# CH32V307_V1_0_0.net
KiCad netlist of a schematic drawn in EasyEDA Pro
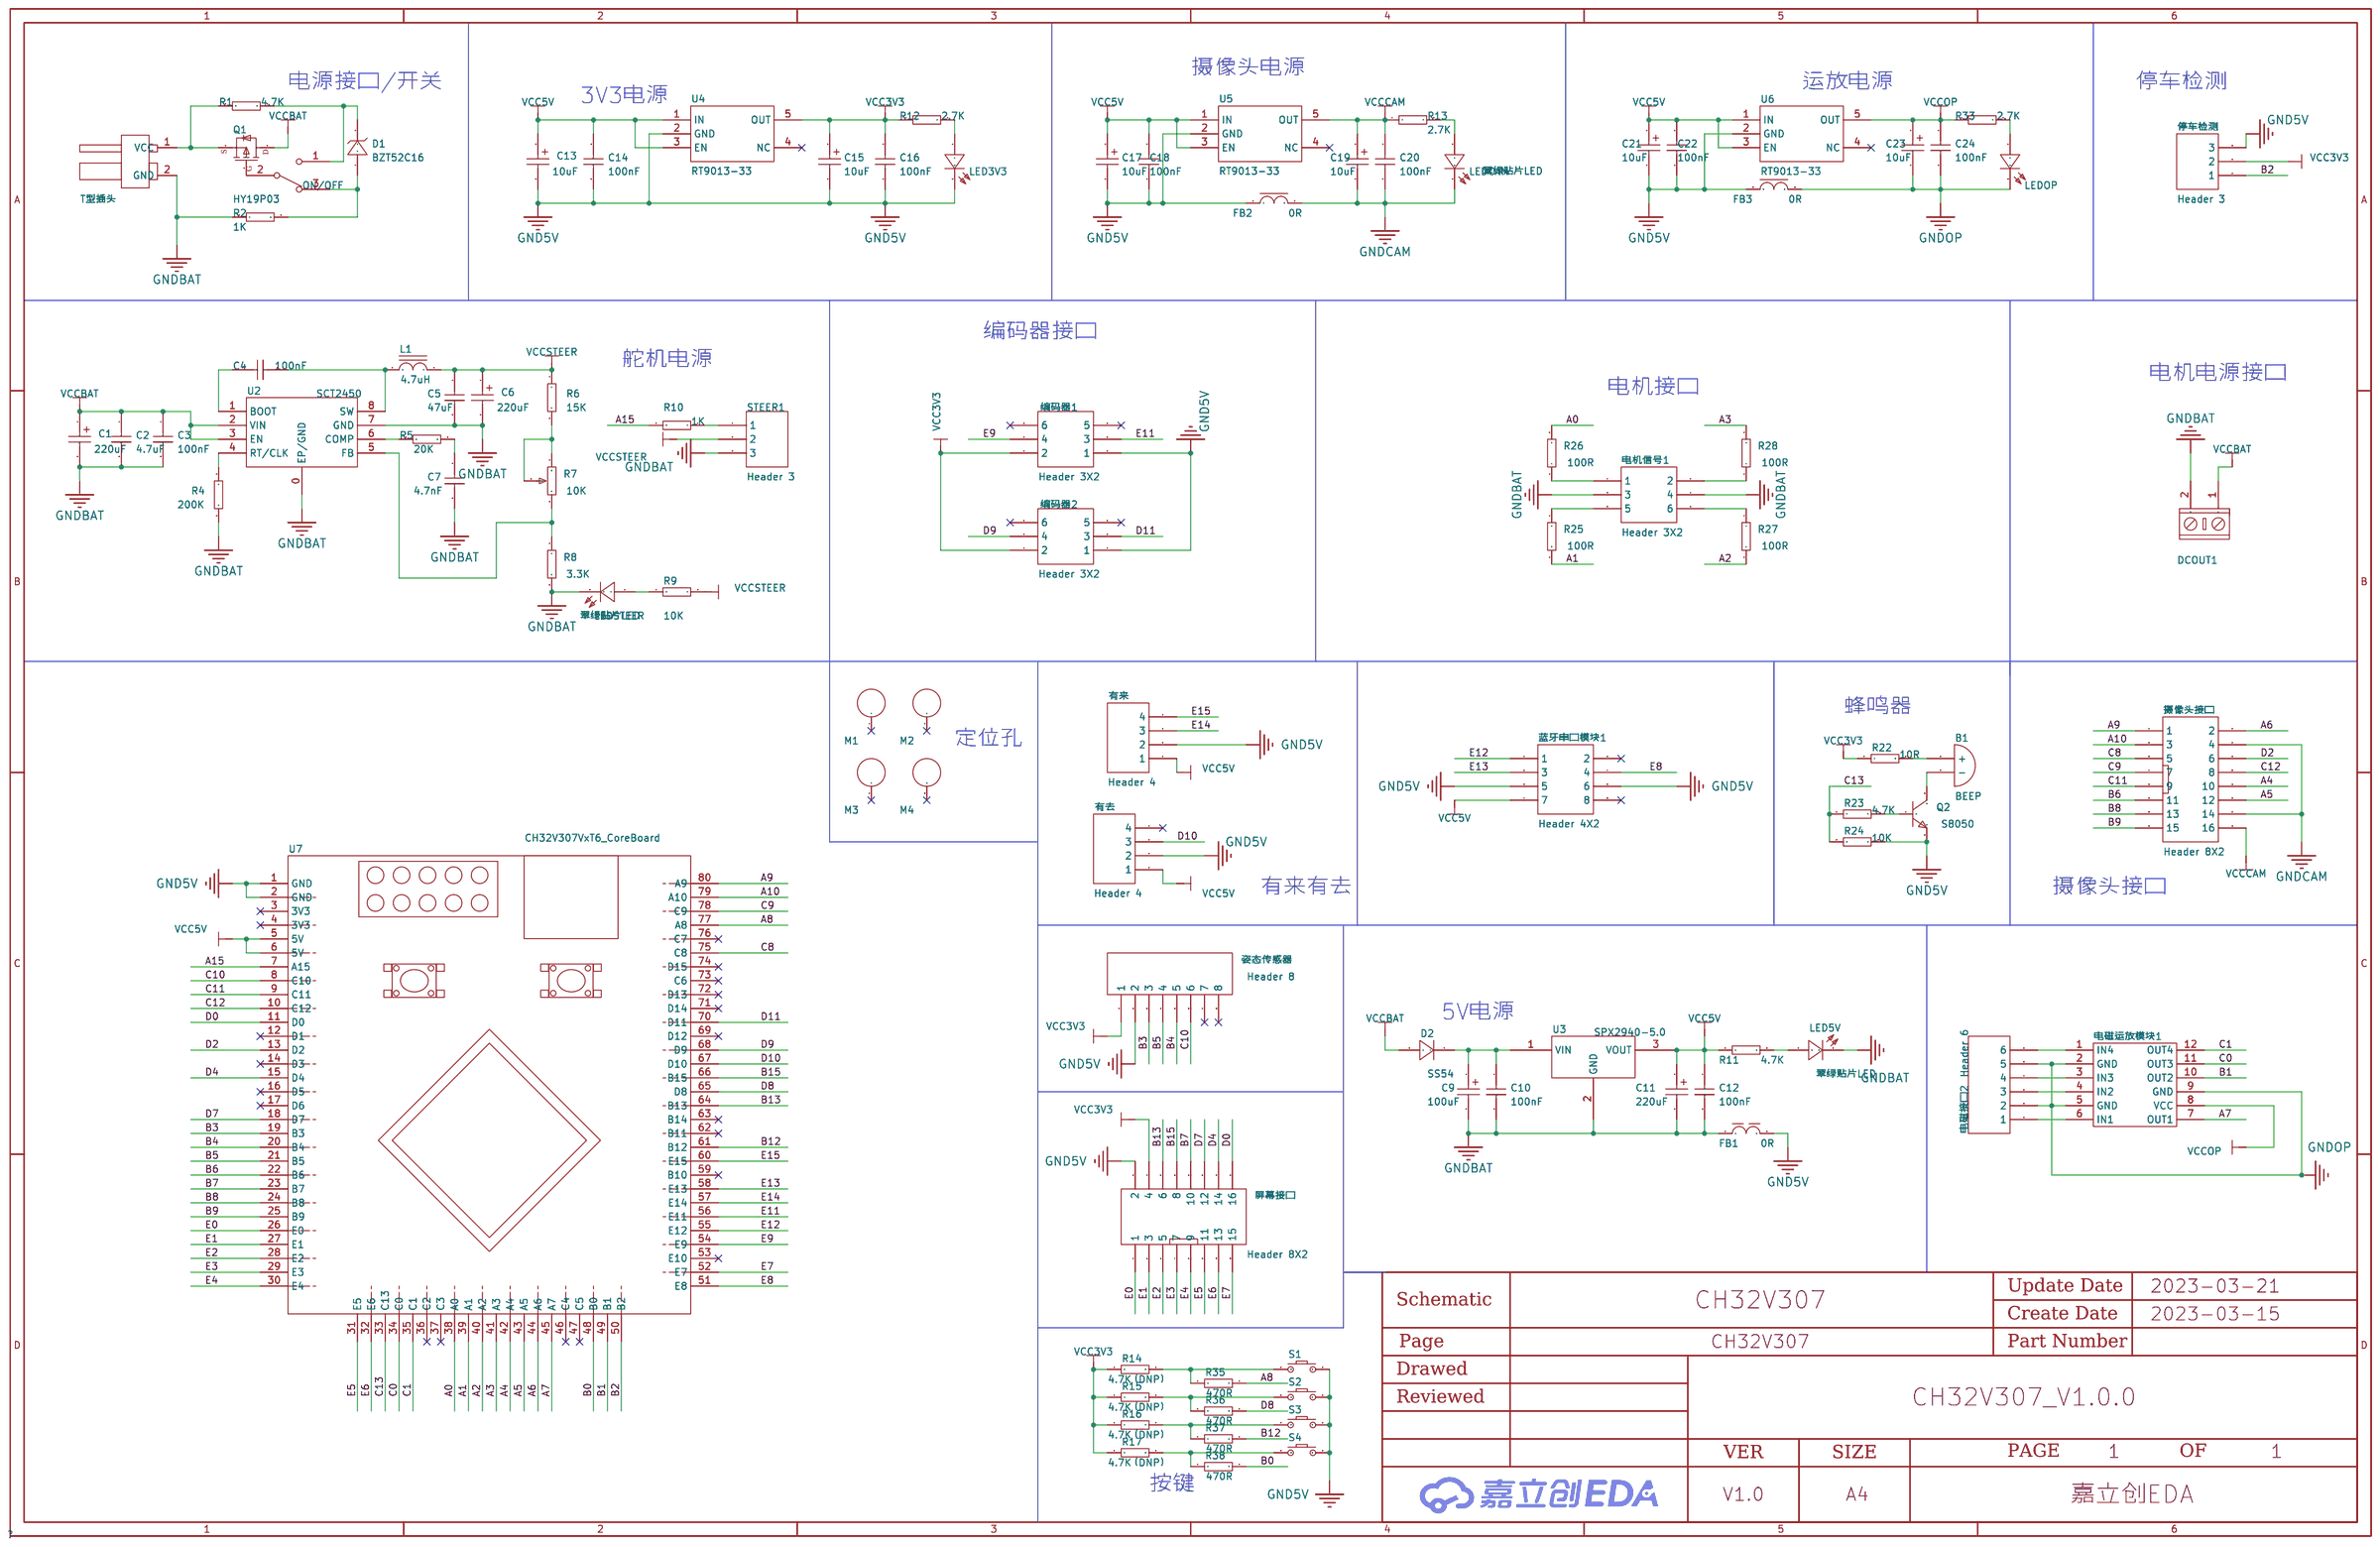
[diagram p0: schematic sheet]

(export (version "E")
  (design (tool "Eeschema 10.0.6"))
  (components
    (comp (ref "B1")
      (value "BEEP")
      (footprint "easyedapro:BEEP 9x5.5mm")
      (libsource (lib "easyedapro") (part "BEEP"))
    )
    (comp (ref "C1")
      (value "220uF")
      (footprint "easyedapro:CAPS6.3")
      (fields (field (name "Voltage") "25V") (field (name "Publisher") "Altium Limited"))
      (libsource (lib "easyedapro") (part "Cap-Solid_1"))
    )
    (comp (ref "C2")
      (value "4.7nF")
      (footprint "easyedapro:CAPC1608[0603]S-N")
      (fields (field (name "Tolerance") "±10%") (field (name "Voltage") "50V"))
      (libsource (lib "easyedapro") (part "Cap-Chip_3"))
    )
    (comp (ref "C3")
      (value "100nF")
      (footprint "easyedapro:CAPC1608[0603]S-N")
      (fields (field (name "Tolerance") "±10%") (field (name "Voltage") "50V"))
      (libsource (lib "easyedapro") (part "Cap-Chip"))
    )
    (comp (ref "C4")
      (value "100nF")
      (footprint "easyedapro:CAPC1608[0603]S-N")
      (libsource (lib "easyedapro") (part "Cap-Chip"))
    )
    (comp (ref "C5")
      (value "47uF")
      (footprint "easyedapro:CAPC3216[1206]S")
      (fields (field (name "Tolerance") "±10%") (field (name "Voltage") "16V"))
      (libsource (lib "easyedapro") (part "Cap-Chip_2"))
    )
    (comp (ref "C6")
      (value "220uF")
      (footprint "easyedapro:CAPS6.3")
      (fields (field (name "Voltage") "25V") (field (name "Publisher") "Altium Limited"))
      (libsource (lib "easyedapro") (part "Cap-Solid_1"))
    )
    (comp (ref "C7")
      (value "4.7nF")
      (footprint "easyedapro:CAPC1608[0603]S-N")
      (fields (field (name "Tolerance") "±10%") (field (name "Voltage") "50V"))
      (libsource (lib "easyedapro") (part "Cap-Chip_3"))
    )
    (comp (ref "C9")
      (value "100uF")
      (footprint "easyedapro:CAPS6.3")
      (fields (field (name "Voltage") "25V") (field (name "Publisher") "Altium Limited"))
      (libsource (lib "easyedapro") (part "Cap-Solid"))
    )
    (comp (ref "C10")
      (value "100nF")
      (footprint "easyedapro:CAPC1608[0603]S-N")
      (fields (field (name "Tolerance") "±10%") (field (name "Voltage") "50V"))
      (libsource (lib "easyedapro") (part "Cap-Chip"))
    )
    (comp (ref "C11")
      (value "220uF")
      (footprint "easyedapro:CAPS6.3")
      (fields (field (name "Voltage") "25V") (field (name "Publisher") "Altium Limited"))
      (libsource (lib "easyedapro") (part "Cap-Solid_1"))
    )
    (comp (ref "C12")
      (value "100nF")
      (footprint "easyedapro:CAPC1608[0603]S-N")
      (fields (field (name "Tolerance") "±10%") (field (name "Voltage") "50V"))
      (libsource (lib "easyedapro") (part "Cap-Chip"))
    )
    (comp (ref "C13")
      (value "10uF")
      (footprint "easyedapro:CAPT3216")
      (fields (field (name "Voltage") "16V") (field (name "Publisher") "Altium Limited"))
      (libsource (lib "easyedapro") (part "Cap-Tan"))
    )
    (comp (ref "C14")
      (value "100nF")
      (footprint "easyedapro:CAPC1608[0603]S-N")
      (fields (field (name "Tolerance") "±10%") (field (name "Voltage") "50V"))
      (libsource (lib "easyedapro") (part "Cap-Chip"))
    )
    (comp (ref "C15")
      (value "10uF")
      (footprint "easyedapro:CAPT3216")
      (fields (field (name "Voltage") "16V") (field (name "Publisher") "Altium Limited"))
      (libsource (lib "easyedapro") (part "Cap-Tan"))
    )
    (comp (ref "C16")
      (value "100nF")
      (footprint "easyedapro:CAPC1608[0603]S-N")
      (fields (field (name "Tolerance") "±10%") (field (name "Voltage") "50V"))
      (libsource (lib "easyedapro") (part "Cap-Chip"))
    )
    (comp (ref "C17")
      (value "10uF")
      (footprint "easyedapro:CAPT3216")
      (fields (field (name "Voltage") "16V") (field (name "Publisher") "Altium Limited"))
      (libsource (lib "easyedapro") (part "Cap-Tan"))
    )
    (comp (ref "C18")
      (value "100nF")
      (footprint "easyedapro:CAPC1608[0603]S-N")
      (fields (field (name "Tolerance") "±10%") (field (name "Voltage") "50V"))
      (libsource (lib "easyedapro") (part "Cap-Chip"))
    )
    (comp (ref "C19")
      (value "10uF")
      (footprint "easyedapro:CAPT3216")
      (fields (field (name "Voltage") "16V") (field (name "Publisher") "Altium Limited"))
      (libsource (lib "easyedapro") (part "Cap-Tan"))
    )
    (comp (ref "C20")
      (value "100nF")
      (footprint "easyedapro:CAPC1608[0603]S-N")
      (fields (field (name "Tolerance") "±10%") (field (name "Voltage") "50V"))
      (libsource (lib "easyedapro") (part "Cap-Chip"))
    )
    (comp (ref "C21")
      (value "10uF")
      (footprint "easyedapro:CAPT3216")
      (fields (field (name "Voltage") "16V") (field (name "Publisher") "Altium Limited"))
      (libsource (lib "easyedapro") (part "Cap-Tan"))
    )
    (comp (ref "C22")
      (value "100nF")
      (footprint "easyedapro:CAPC1608[0603]S-N")
      (fields (field (name "Tolerance") "±10%") (field (name "Voltage") "50V"))
      (libsource (lib "easyedapro") (part "Cap-Chip"))
    )
    (comp (ref "C23")
      (value "10uF")
      (footprint "easyedapro:CAPT3216")
      (fields (field (name "Voltage") "16V") (field (name "Publisher") "Altium Limited"))
      (libsource (lib "easyedapro") (part "Cap-Tan"))
    )
    (comp (ref "C24")
      (value "100nF")
      (footprint "easyedapro:CAPC1608[0603]S-N")
      (fields (field (name "Tolerance") "±10%") (field (name "Voltage") "50V"))
      (libsource (lib "easyedapro") (part "Cap-Chip"))
    )
    (comp (ref "D1")
      (value "BZT52C16")
      (footprint "easyedapro:SOD-123-L")
      (fields (field (name "Publisher") "Altium Limited"))
      (libsource (lib "easyedapro") (part "Diode TVS Uni-Dir"))
    )
    (comp (ref "D2")
      (value "SS54")
      (footprint "easyedapro:SMA[DO-214AC]")
      (libsource (lib "easyedapro") (part "Diode"))
    )
    (comp (ref "DCOUT1")
      (value "KF/WJ/DG 30x connecter")
      (footprint "easyedapro:KF/WJ/DG 301-2p-5.0mm")
      (libsource (lib "easyedapro") (part "KF/WJ/DG 30x"))
    )
    (comp (ref "FB1")
      (value "0R")
      (footprint "easyedapro:INDC2012[0805]S")
      (libsource (lib "easyedapro") (part "Ind Chip 2"))
    )
    (comp (ref "FB2")
      (value "0R")
      (footprint "easyedapro:INDC2012[0805]S")
      (libsource (lib "easyedapro") (part "Ind-Chip"))
    )
    (comp (ref "FB3")
      (value "0R")
      (footprint "easyedapro:INDC2012[0805]S")
      (libsource (lib "easyedapro") (part "Ind-Chip"))
    )
    (comp (ref "L1")
      (value "4.7uH")
      (footprint "easyedapro:0630 TPC 7*7*3")
      (libsource (lib "easyedapro") (part "Ind-Power"))
    )
    (comp (ref "LED3V3")
      (value "翠绿贴片LED")
      (footprint "easyedapro:LEDC1608(0603)")
      (fields (field (name "Publisher") "Altium Limited"))
      (libsource (lib "easyedapro") (part "LED Chip Green"))
    )
    (comp (ref "LED5V")
      (value "翠绿贴片LED")
      (footprint "easyedapro:LEDC1608(0603)")
      (libsource (lib "easyedapro") (part "LED Chip Green"))
    )
    (comp (ref "LEDCAM")
      (value "翠绿贴片LED")
      (footprint "easyedapro:LEDC1608(0603)")
      (fields (field (name "Publisher") "Altium Limited"))
      (libsource (lib "easyedapro") (part "LED Chip Green"))
    )
    (comp (ref "LEDOP")
      (value "翠绿贴片LED")
      (footprint "easyedapro:LEDC1608(0603)")
      (fields (field (name "Publisher") "Altium Limited"))
      (libsource (lib "easyedapro") (part "LED Chip Green"))
    )
    (comp (ref "LEDSTEER")
      (value "翠绿贴片LED")
      (footprint "easyedapro:LEDC1608(0603)")
      (fields (field (name "Publisher") "Altium Limited"))
      (libsource (lib "easyedapro") (part "LED Chip Green"))
    )
    (comp (ref "M1")
      (value "MountHole")
      (footprint "easyedapro:M3-MountHole-Plated")
      (libsource (lib "easyedapro") (part "MountHole"))
    )
    (comp (ref "M2")
      (value "MountHole")
      (footprint "easyedapro:M3-MountHole-Plated")
      (libsource (lib "easyedapro") (part "MountHole"))
    )
    (comp (ref "M3")
      (value "MountHole")
      (footprint "easyedapro:M3-MountHole-Plated")
      (libsource (lib "easyedapro") (part "MountHole"))
    )
    (comp (ref "M4")
      (value "MountHole")
      (footprint "easyedapro:M3-MountHole-Plated")
      (libsource (lib "easyedapro") (part "MountHole"))
    )
    (comp (ref "ON/OFF")
      (value "SW-SPDT")
      (footprint "easyedapro:SS12D10")
      (fields (field (name "Publisher") "Altium Limited"))
      (libsource (lib "easyedapro") (part "SW-SPDT"))
    )
    (comp (ref "Q1")
      (value "HY19P03")
      (footprint "easyedapro:TO-252AA")
      (libsource (lib "easyedapro") (part "HY19P03"))
    )
    (comp (ref "Q2")
      (value "S8050")
      (footprint "easyedapro:SOT-23")
      (libsource (lib "easyedapro") (part "NPN S8050"))
    )
    (comp (ref "R1")
      (value "4.7K")
      (footprint "easyedapro:RESC1608[0603]S-N")
      (libsource (lib "easyedapro") (part "Res-Chip_2"))
    )
    (comp (ref "R2")
      (value "1K")
      (footprint "easyedapro:RESC1608[0603]S-N")
      (libsource (lib "easyedapro") (part "Res-Chip_1"))
    )
    (comp (ref "R4")
      (value "200K")
      (footprint "easyedapro:RESC1608[0603]S-N")
      (fields (field (name "Tolerance") "±1%"))
      (libsource (lib "easyedapro") (part "Res-Chip_4"))
    )
    (comp (ref "R5")
      (value "20K")
      (footprint "easyedapro:RESC1608[0603]S-N")
      (libsource (lib "easyedapro") (part "Res-Chip_5"))
    )
    (comp (ref "R6")
      (value "15K")
      (footprint "easyedapro:RESC1608[0603]S-N")
      (fields (field (name "Tolerance") "±1%"))
      (libsource (lib "easyedapro") (part "Res-Chip_6"))
    )
    (comp (ref "R7")
      (value "10K")
      (footprint "easyedapro:RESPOT3296")
      (libsource (lib "easyedapro") (part "Res-Adj-3p"))
    )
    (comp (ref "R8")
      (value "3.3K")
      (footprint "easyedapro:RESC1608[0603]S-N")
      (fields (field (name "Tolerance") "±1%"))
      (libsource (lib "easyedapro") (part "Res-Chip_7"))
    )
    (comp (ref "R9")
      (value "10K")
      (footprint "easyedapro:RESC1608[0603]S-N")
      (libsource (lib "easyedapro") (part "Res-Chip"))
    )
    (comp (ref "R10")
      (value "1K")
      (footprint "easyedapro:RESC1608[0603]S-N")
      (fields (field (name "Tolerance") "±1%"))
      (libsource (lib "easyedapro") (part "Res-Chip_1"))
    )
    (comp (ref "R11")
      (value "4.7K")
      (footprint "easyedapro:RESC1608[0603]S-N")
      (libsource (lib "easyedapro") (part "Res-Chip_2"))
    )
    (comp (ref "R12")
      (value "2.7K")
      (footprint "easyedapro:RESC1608[0603]S-N")
      (libsource (lib "easyedapro") (part "Res-Chip_3"))
    )
    (comp (ref "R13")
      (value "2.7K")
      (footprint "easyedapro:RESC1608[0603]S-N")
      (libsource (lib "easyedapro") (part "Res-Chip_3"))
    )
    (comp (ref "R14")
      (value "4.7K(DNP)")
      (footprint "easyedapro:RESC1608[0603]S-N")
      (libsource (lib "easyedapro") (part "Res-Chip_9"))
    )
    (comp (ref "R15")
      (value "4.7K(DNP)")
      (footprint "easyedapro:RESC1608[0603]S-N")
      (libsource (lib "easyedapro") (part "Res-Chip_9"))
    )
    (comp (ref "R16")
      (value "4.7K(DNP)")
      (footprint "easyedapro:RESC1608[0603]S-N")
      (libsource (lib "easyedapro") (part "Res-Chip_9"))
    )
    (comp (ref "R17")
      (value "4.7K(DNP)")
      (footprint "easyedapro:RESC1608[0603]S-N")
      (libsource (lib "easyedapro") (part "Res-Chip_9"))
    )
    (comp (ref "R22")
      (value "10R")
      (footprint "easyedapro:RESC1608[0603]S-N")
      (libsource (lib "easyedapro") (part "Res-Chip_10"))
    )
    (comp (ref "R23")
      (value "4.7K")
      (footprint "easyedapro:RESC1608[0603]S-N")
      (libsource (lib "easyedapro") (part "Res-Chip_2"))
    )
    (comp (ref "R24")
      (value "10K")
      (footprint "easyedapro:RESC1608[0603]S-N")
      (libsource (lib "easyedapro") (part "Res-Chip"))
    )
    (comp (ref "R25")
      (value "100R")
      (footprint "easyedapro:RESC1608[0603]S-N")
      (libsource (lib "easyedapro") (part "Res-Chip_8"))
    )
    (comp (ref "R26")
      (value "100R")
      (footprint "easyedapro:RESC1608[0603]S-N")
      (libsource (lib "easyedapro") (part "Res-Chip_8"))
    )
    (comp (ref "R27")
      (value "100R")
      (footprint "easyedapro:RESC1608[0603]S-N")
      (fields (field (name "Tolerance") "±1%"))
      (libsource (lib "easyedapro") (part "Res-Chip_8"))
    )
    (comp (ref "R28")
      (value "100R")
      (footprint "easyedapro:RESC1608[0603]S-N")
      (libsource (lib "easyedapro") (part "Res-Chip_8"))
    )
    (comp (ref "R33")
      (value "2.7K")
      (footprint "easyedapro:RESC1608[0603]S-N")
      (libsource (lib "easyedapro") (part "Res-Chip_3"))
    )
    (comp (ref "R35")
      (value "470R")
      (footprint "easyedapro:RESC1608[0603]S-N")
      (libsource (lib "easyedapro") (part "Res-Chip_11"))
    )
    (comp (ref "R36")
      (value "470R")
      (footprint "easyedapro:RESC1608[0603]S-N")
      (libsource (lib "easyedapro") (part "Res-Chip_11"))
    )
    (comp (ref "R37")
      (value "470R")
      (footprint "easyedapro:RESC1608[0603]S-N")
      (libsource (lib "easyedapro") (part "Res-Chip_11"))
    )
    (comp (ref "R38")
      (value "470R")
      (footprint "easyedapro:RESC1608[0603]S-N")
      (libsource (lib "easyedapro") (part "Res-Chip_11"))
    )
    (comp (ref "S1")
      (value "Button")
      (footprint "easyedapro:PTS810-3*4-CurvePin")
      (libsource (lib "easyedapro") (part "KEY"))
    )
    (comp (ref "S2")
      (value "Button")
      (footprint "easyedapro:PTS810-3*4-CurvePin")
      (libsource (lib "easyedapro") (part "KEY"))
    )
    (comp (ref "S3")
      (value "Button")
      (footprint "easyedapro:PTS810-3*4-CurvePin")
      (libsource (lib "easyedapro") (part "KEY"))
    )
    (comp (ref "S4")
      (value "Button")
      (footprint "easyedapro:PTS810-3*4-CurvePin")
      (libsource (lib "easyedapro") (part "KEY"))
    )
    (comp (ref "STEER1")
      (value "Header 3")
      (footprint "easyedapro:HDR1X3")
      (fields (field (name "Publisher") "Altium Limited"))
      (libsource (lib "easyedapro") (part "Header 3"))
    )
    (comp (ref "U1")
      (value "T型插头")
      (footprint "easyedapro:Wired T-Header ThroughHole")
      (libsource (lib "easyedapro") (part "T_Header"))
    )
    (comp (ref "U2")
      (value "SCT2450")
      (footprint "easyedapro:SOP-8E")
      (libsource (lib "easyedapro") (part "SCT2450"))
    )
    (comp (ref "U3")
      (value "SPX2940-5.0")
      (footprint "easyedapro:TO-263-3")
      (libsource (lib "easyedapro") (part "LM2940-5.0"))
    )
    (comp (ref "U4")
      (value "RT9013-33")
      (footprint "easyedapro:SOT-23-5")
      (libsource (lib "easyedapro") (part "RT9013-33"))
    )
    (comp (ref "U5")
      (value "RT9013-33")
      (footprint "easyedapro:SOT-23-5")
      (libsource (lib "easyedapro") (part "RT9013-33"))
    )
    (comp (ref "U6")
      (value "RT9013-33")
      (footprint "easyedapro:SOT-23-5")
      (libsource (lib "easyedapro") (part "RT9013-33"))
    )
    (comp (ref "U7")
      (value "CH32V307VxT6_CoreBoard")
      (footprint "easyedapro:CH32V307VxT6_CoreBoard")
      (libsource (lib "easyedapro") (part "CH32V307VxT6_CoreBoardV1.3"))
    )
    (comp (ref "停车检测")
      (value "Header 3")
      (footprint "easyedapro:HDR1X3")
      (fields (field (name "Publisher") "Altium Limited"))
      (libsource (lib "easyedapro") (part "Header 3"))
    )
    (comp (ref "姿态传感器")
      (value "Header 8")
      (footprint "easyedapro:HDR1X8")
      (fields (field (name "Publisher") "Altium Limited"))
      (libsource (lib "easyedapro") (part "Header 8"))
    )
    (comp (ref "屏幕接口")
      (value "Header 8X2")
      (footprint "easyedapro:HDR2X8-M-SMT")
      (fields (field (name "Publisher") "Altium Limited"))
      (libsource (lib "easyedapro") (part "Header 8X2"))
    )
    (comp (ref "摄像头接口")
      (value "Header 8X2")
      (footprint "easyedapro:HDR2X8-M-SMT")
      (libsource (lib "easyedapro") (part "Header 8X2"))
    )
    (comp (ref "有去")
      (value "Header 4")
      (footprint "easyedapro:HDR1X4")
      (fields (field (name "Publisher") "Altium Limited"))
      (libsource (lib "easyedapro") (part "Header 4"))
    )
    (comp (ref "有来")
      (value "Header 4")
      (footprint "easyedapro:HDR1X4")
      (fields (field (name "Publisher") "Altium Limited"))
      (libsource (lib "easyedapro") (part "Header 4"))
    )
    (comp (ref "电机信号1")
      (value "Header 3X2")
      (footprint "easyedapro:HDR2X3-M-SMT")
      (libsource (lib "easyedapro") (part "Header 3X2"))
    )
    (comp (ref "电磁接口2")
      (value "Header 6")
      (footprint "easyedapro:HDR1X6")
      (libsource (lib "easyedapro") (part "Header 6"))
    )
    (comp (ref "电磁运放模块1")
      (value "OPA_MOD")
      (footprint "easyedapro:SEEKFREE_4CHANEL_OPAMOD")
      (libsource (lib "easyedapro") (part "OPA_4CHANNEL_SEEKFREE"))
    )
    (comp (ref "编码器1")
      (value "Header 3X2")
      (footprint "easyedapro:HDR2X3-M-SMT")
      (fields (field (name "Publisher") "Altium Limited"))
      (libsource (lib "easyedapro") (part "Header 3X2"))
    )
    (comp (ref "编码器2")
      (value "Header 3X2")
      (footprint "easyedapro:HDR2X3-M-SMT")
      (fields (field (name "Publisher") "Altium Limited"))
      (libsource (lib "easyedapro") (part "Header 3X2"))
    )
    (comp (ref "蓝牙串口模块1")
      (value "Header 4X2")
      (footprint "easyedapro:Female-Header-2.54-SMD-8")
      (libsource (lib "easyedapro") (part "Header 4X2"))
    )
  )
  (nets
    (net (code "1") (name "/A0") (class "Default")
      (node (ref "R26") (pin "2") (pinfunction "2_2") (pintype "input"))
      (node (ref "U7") (pin "38") (pinfunction "A0_38") (pintype "input"))
    )
    (net (code "2") (name "/A1") (class "Default")
      (node (ref "R25") (pin "2") (pinfunction "2_2") (pintype "input"))
      (node (ref "U7") (pin "39") (pinfunction "A1_39") (pintype "input"))
    )
    (net (code "3") (name "/A2") (class "Default")
      (node (ref "R27") (pin "2") (pinfunction "2_2") (pintype "input"))
      (node (ref "U7") (pin "40") (pinfunction "A2_40") (pintype "input"))
    )
    (net (code "4") (name "/A3") (class "Default")
      (node (ref "R28") (pin "2") (pinfunction "2_2") (pintype "input"))
      (node (ref "U7") (pin "41") (pinfunction "A3_41") (pintype "input"))
    )
    (net (code "5") (name "/A4") (class "Default")
      (node (ref "U7") (pin "42") (pinfunction "A4_42") (pintype "input"))
      (node (ref "摄像头接口") (pin "10") (pinfunction "10_10") (pintype "input"))
    )
    (net (code "6") (name "/A5") (class "Default")
      (node (ref "U7") (pin "43") (pinfunction "A5_43") (pintype "input"))
      (node (ref "摄像头接口") (pin "12") (pinfunction "12_12") (pintype "input"))
    )
    (net (code "7") (name "/A6") (class "Default")
      (node (ref "U7") (pin "44") (pinfunction "A6_44") (pintype "input"))
      (node (ref "摄像头接口") (pin "2") (pinfunction "2_2") (pintype "input"))
    )
    (net (code "8") (name "/A7") (class "Default")
      (node (ref "U7") (pin "45") (pinfunction "A7_45") (pintype "input"))
      (node (ref "电磁运放模块1") (pin "7") (pinfunction "OUT1_7") (pintype "input"))
    )
    (net (code "9") (name "/A8") (class "Default")
      (node (ref "R35") (pin "2") (pinfunction "2_2") (pintype "input"))
      (node (ref "U7") (pin "77") (pinfunction "A8_77") (pintype "input"))
    )
    (net (code "10") (name "/A9") (class "Default")
      (node (ref "U7") (pin "80") (pinfunction "A9_80") (pintype "input"))
      (node (ref "摄像头接口") (pin "1") (pinfunction "1_1") (pintype "input"))
    )
    (net (code "11") (name "/A10") (class "Default")
      (node (ref "U7") (pin "79") (pinfunction "A10_79") (pintype "input"))
      (node (ref "摄像头接口") (pin "3") (pinfunction "3_3") (pintype "input"))
    )
    (net (code "12") (name "/A15") (class "Default")
      (node (ref "R10") (pin "2") (pinfunction "2_2") (pintype "input"))
      (node (ref "U7") (pin "7") (pinfunction "A15_7") (pintype "input"))
    )
    (net (code "13") (name "/B0") (class "Default")
      (node (ref "R38") (pin "2") (pinfunction "2_2") (pintype "input"))
      (node (ref "U7") (pin "48") (pinfunction "B0_48") (pintype "input"))
    )
    (net (code "14") (name "/B1") (class "Default")
      (node (ref "U7") (pin "49") (pinfunction "B1_49") (pintype "input"))
      (node (ref "电磁运放模块1") (pin "10") (pinfunction "OUT2_10") (pintype "input"))
    )
    (net (code "15") (name "/B2") (class "Default")
      (node (ref "U7") (pin "50") (pinfunction "B2_50") (pintype "input"))
      (node (ref "停车检测") (pin "1") (pinfunction "1_1") (pintype "input"))
    )
    (net (code "16") (name "/B3") (class "Default")
      (node (ref "U7") (pin "19") (pinfunction "B3_19") (pintype "input"))
      (node (ref "姿态传感器") (pin "3") (pinfunction "3_3") (pintype "input"))
    )
    (net (code "17") (name "/B4") (class "Default")
      (node (ref "U7") (pin "20") (pinfunction "B4_20") (pintype "input"))
      (node (ref "姿态传感器") (pin "5") (pinfunction "5_5") (pintype "input"))
    )
    (net (code "18") (name "/B5") (class "Default")
      (node (ref "U7") (pin "21") (pinfunction "B5_21") (pintype "input"))
      (node (ref "姿态传感器") (pin "4") (pinfunction "4_4") (pintype "input"))
    )
    (net (code "19") (name "/B6") (class "Default")
      (node (ref "U7") (pin "22") (pinfunction "B6_22") (pintype "input"))
      (node (ref "摄像头接口") (pin "11") (pinfunction "11_11") (pintype "input"))
    )
    (net (code "20") (name "/B7") (class "Default")
      (node (ref "U7") (pin "23") (pinfunction "B7_23") (pintype "input"))
      (node (ref "屏幕接口") (pin "10") (pinfunction "10_10") (pintype "input"))
    )
    (net (code "21") (name "/B8") (class "Default")
      (node (ref "U7") (pin "24") (pinfunction "B8_24") (pintype "input"))
      (node (ref "摄像头接口") (pin "13") (pinfunction "13_13") (pintype "input"))
    )
    (net (code "22") (name "/B9") (class "Default")
      (node (ref "U7") (pin "25") (pinfunction "B9_25") (pintype "input"))
      (node (ref "摄像头接口") (pin "15") (pinfunction "15_15") (pintype "input"))
    )
    (net (code "23") (name "/B12") (class "Default")
      (node (ref "R37") (pin "2") (pinfunction "2_2") (pintype "input"))
      (node (ref "U7") (pin "61") (pinfunction "B12_61") (pintype "input"))
    )
    (net (code "24") (name "/B13") (class "Default")
      (node (ref "U7") (pin "64") (pinfunction "B13_64") (pintype "input"))
      (node (ref "屏幕接口") (pin "6") (pinfunction "6_6") (pintype "input"))
    )
    (net (code "25") (name "/B15") (class "Default")
      (node (ref "U7") (pin "66") (pinfunction "B15_66") (pintype "input"))
      (node (ref "屏幕接口") (pin "8") (pinfunction "8_8") (pintype "input"))
    )
    (net (code "26") (name "/C0") (class "Default")
      (node (ref "U7") (pin "34") (pinfunction "C0_34") (pintype "input"))
      (node (ref "电磁运放模块1") (pin "11") (pinfunction "OUT3_11") (pintype "input"))
    )
    (net (code "27") (name "/C1") (class "Default")
      (node (ref "U7") (pin "35") (pinfunction "C1_35") (pintype "input"))
      (node (ref "电磁运放模块1") (pin "12") (pinfunction "OUT4_12") (pintype "input"))
    )
    (net (code "28") (name "/C8") (class "Default")
      (node (ref "U7") (pin "75") (pinfunction "C8_75") (pintype "input"))
      (node (ref "摄像头接口") (pin "5") (pinfunction "5_5") (pintype "input"))
    )
    (net (code "29") (name "/C9") (class "Default")
      (node (ref "U7") (pin "78") (pinfunction "C9_78") (pintype "input"))
      (node (ref "摄像头接口") (pin "7") (pinfunction "7_7") (pintype "input"))
    )
    (net (code "30") (name "/C10") (class "Default")
      (node (ref "U7") (pin "8") (pinfunction "C10_8") (pintype "input"))
      (node (ref "姿态传感器") (pin "6") (pinfunction "6_6") (pintype "input"))
    )
    (net (code "31") (name "/C11") (class "Default")
      (node (ref "U7") (pin "9") (pinfunction "C11_9") (pintype "input"))
      (node (ref "摄像头接口") (pin "9") (pinfunction "9_9") (pintype "input"))
    )
    (net (code "32") (name "/C12") (class "Default")
      (node (ref "U7") (pin "10") (pinfunction "C12_10") (pintype "input"))
      (node (ref "摄像头接口") (pin "8") (pinfunction "8_8") (pintype "input"))
    )
    (net (code "33") (name "/C13") (class "Default")
      (node (ref "R23") (pin "1") (pinfunction "1_1") (pintype "input"))
      (node (ref "R24") (pin "1") (pinfunction "1_1") (pintype "input"))
      (node (ref "U7") (pin "33") (pinfunction "C13_33") (pintype "input"))
    )
    (net (code "34") (name "/D0") (class "Default")
      (node (ref "U7") (pin "11") (pinfunction "D0_11") (pintype "input"))
      (node (ref "屏幕接口") (pin "16") (pinfunction "16_16") (pintype "input"))
    )
    (net (code "35") (name "/D2") (class "Default")
      (node (ref "U7") (pin "13") (pinfunction "D2_13") (pintype "input"))
      (node (ref "摄像头接口") (pin "6") (pinfunction "6_6") (pintype "input"))
    )
    (net (code "36") (name "/D4") (class "Default")
      (node (ref "U7") (pin "15") (pinfunction "D4_15") (pintype "input"))
      (node (ref "屏幕接口") (pin "14") (pinfunction "14_14") (pintype "input"))
    )
    (net (code "37") (name "/D7") (class "Default")
      (node (ref "U7") (pin "18") (pinfunction "D7_18") (pintype "input"))
      (node (ref "屏幕接口") (pin "12") (pinfunction "12_12") (pintype "input"))
    )
    (net (code "38") (name "/D8") (class "Default")
      (node (ref "R36") (pin "2") (pinfunction "2_2") (pintype "input"))
      (node (ref "U7") (pin "65") (pinfunction "D8_65") (pintype "input"))
    )
    (net (code "39") (name "/D9") (class "Default")
      (node (ref "U7") (pin "68") (pinfunction "D9_68") (pintype "input"))
      (node (ref "编码器2") (pin "4") (pinfunction "4_4") (pintype "input"))
    )
    (net (code "40") (name "/D10") (class "Default")
      (node (ref "U7") (pin "67") (pinfunction "D10_67") (pintype "input"))
      (node (ref "有去") (pin "3") (pinfunction "3_3") (pintype "input"))
    )
    (net (code "41") (name "/D11") (class "Default")
      (node (ref "U7") (pin "70") (pinfunction "D11_70") (pintype "input"))
      (node (ref "编码器2") (pin "3") (pinfunction "3_3") (pintype "input"))
    )
    (net (code "42") (name "/E0") (class "Default")
      (node (ref "U7") (pin "26") (pinfunction "E0_26") (pintype "input"))
      (node (ref "屏幕接口") (pin "1") (pinfunction "1_1") (pintype "input"))
    )
    (net (code "43") (name "/E1") (class "Default")
      (node (ref "U7") (pin "27") (pinfunction "E1_27") (pintype "input"))
      (node (ref "屏幕接口") (pin "3") (pinfunction "3_3") (pintype "input"))
    )
    (net (code "44") (name "/E2") (class "Default")
      (node (ref "U7") (pin "28") (pinfunction "E2_28") (pintype "input"))
      (node (ref "屏幕接口") (pin "5") (pinfunction "5_5") (pintype "input"))
    )
    (net (code "45") (name "/E3") (class "Default")
      (node (ref "U7") (pin "29") (pinfunction "E3_29") (pintype "input"))
      (node (ref "屏幕接口") (pin "7") (pinfunction "7_7") (pintype "input"))
    )
    (net (code "46") (name "/E4") (class "Default")
      (node (ref "U7") (pin "30") (pinfunction "E4_30") (pintype "input"))
      (node (ref "屏幕接口") (pin "9") (pinfunction "9_9") (pintype "input"))
    )
    (net (code "47") (name "/E5") (class "Default")
      (node (ref "U7") (pin "31") (pinfunction "E5_31") (pintype "input"))
      (node (ref "屏幕接口") (pin "11") (pinfunction "11_11") (pintype "input"))
    )
    (net (code "48") (name "/E6") (class "Default")
      (node (ref "U7") (pin "32") (pinfunction "E6_32") (pintype "input"))
      (node (ref "屏幕接口") (pin "13") (pinfunction "13_13") (pintype "input"))
    )
    (net (code "49") (name "/E7") (class "Default")
      (node (ref "U7") (pin "52") (pinfunction "E7_52") (pintype "input"))
      (node (ref "屏幕接口") (pin "15") (pinfunction "15_15") (pintype "input"))
    )
    (net (code "50") (name "/E8") (class "Default")
      (node (ref "U7") (pin "51") (pinfunction "E8_51") (pintype "input"))
      (node (ref "蓝牙串口模块1") (pin "4") (pinfunction "4_4") (pintype "input"))
    )
    (net (code "51") (name "/E9") (class "Default")
      (node (ref "U7") (pin "54") (pinfunction "E9_54") (pintype "input"))
      (node (ref "编码器1") (pin "4") (pinfunction "4_4") (pintype "input"))
    )
    (net (code "52") (name "/E11") (class "Default")
      (node (ref "U7") (pin "56") (pinfunction "E11_56") (pintype "input"))
      (node (ref "编码器1") (pin "3") (pinfunction "3_3") (pintype "input"))
    )
    (net (code "53") (name "/E12") (class "Default")
      (node (ref "U7") (pin "55") (pinfunction "E12_55") (pintype "input"))
      (node (ref "蓝牙串口模块1") (pin "1") (pinfunction "1_1") (pintype "input"))
    )
    (net (code "54") (name "/E13") (class "Default")
      (node (ref "U7") (pin "58") (pinfunction "E13_58") (pintype "input"))
      (node (ref "蓝牙串口模块1") (pin "3") (pinfunction "3_3") (pintype "input"))
    )
    (net (code "55") (name "/E14") (class "Default")
      (node (ref "U7") (pin "57") (pinfunction "E14_57") (pintype "input"))
      (node (ref "有来") (pin "3") (pinfunction "3_3") (pintype "input"))
    )
    (net (code "56") (name "/E15") (class "Default")
      (node (ref "U7") (pin "60") (pinfunction "E15_60") (pintype "input"))
      (node (ref "有来") (pin "4") (pinfunction "4_4") (pintype "input"))
    )
    (net (code "57") (name "GND5V") (class "Default")
      (node (ref "C13") (pin "2") (pinfunction "2_2") (pintype "input"))
      (node (ref "C14") (pin "2") (pinfunction "2_2") (pintype "input"))
      (node (ref "C15") (pin "2") (pinfunction "2_2") (pintype "input"))
      (node (ref "C16") (pin "2") (pinfunction "2_2") (pintype "input"))
      (node (ref "C17") (pin "2") (pinfunction "2_2") (pintype "input"))
      (node (ref "C18") (pin "2") (pinfunction "2_2") (pintype "input"))
      (node (ref "C21") (pin "2") (pinfunction "2_2") (pintype "input"))
      (node (ref "C22") (pin "2") (pinfunction "2_2") (pintype "input"))
      (node (ref "FB1") (pin "2") (pinfunction "2_2") (pintype "input"))
      (node (ref "FB2") (pin "1") (pinfunction "1_1") (pintype "input"))
      (node (ref "FB3") (pin "1") (pinfunction "1_1") (pintype "input"))
      (node (ref "LED3V3") (pin "C") (pinfunction "C_C") (pintype "input"))
      (node (ref "Q2") (pin "2") (pinfunction "E_2") (pintype "input"))
      (node (ref "R24") (pin "2") (pinfunction "2_2") (pintype "input"))
      (node (ref "S1") (pin "1") (pinfunction "1_1") (pintype "input"))
      (node (ref "S2") (pin "1") (pinfunction "1_1") (pintype "input"))
      (node (ref "S3") (pin "1") (pinfunction "1_1") (pintype "input"))
      (node (ref "S4") (pin "1") (pinfunction "1_1") (pintype "input"))
      (node (ref "U4") (pin "2") (pinfunction "GND_2") (pintype "input"))
      (node (ref "U5") (pin "2") (pinfunction "GND_2") (pintype "input"))
      (node (ref "U6") (pin "2") (pinfunction "GND_2") (pintype "input"))
      (node (ref "U7") (pin "1") (pinfunction "GND_1") (pintype "input"))
      (node (ref "U7") (pin "2") (pinfunction "GND_2") (pintype "input"))
      (node (ref "停车检测") (pin "3") (pinfunction "3_3") (pintype "input"))
      (node (ref "姿态传感器") (pin "2") (pinfunction "2_2") (pintype "input"))
      (node (ref "屏幕接口") (pin "2") (pinfunction "2_2") (pintype "input"))
      (node (ref "有去") (pin "2") (pinfunction "2_2") (pintype "input"))
      (node (ref "有来") (pin "2") (pinfunction "2_2") (pintype "input"))
      (node (ref "编码器1") (pin "1") (pinfunction "1_1") (pintype "input"))
      (node (ref "编码器2") (pin "1") (pinfunction "1_1") (pintype "input"))
      (node (ref "蓝牙串口模块1") (pin "5") (pinfunction "5_5") (pintype "input"))
      (node (ref "蓝牙串口模块1") (pin "6") (pinfunction "6_6") (pintype "input"))
    )
    (net (code "58") (name "GNDBAT") (class "Default")
      (node (ref "C1") (pin "2") (pinfunction "2_2") (pintype "input"))
      (node (ref "C10") (pin "2") (pinfunction "2_2") (pintype "input"))
      (node (ref "C11") (pin "2") (pinfunction "2_2") (pintype "input"))
      (node (ref "C12") (pin "2") (pinfunction "2_2") (pintype "input"))
      (node (ref "C2") (pin "2") (pinfunction "2_2") (pintype "input"))
      (node (ref "C3") (pin "2") (pinfunction "2_2") (pintype "input"))
      (node (ref "C5") (pin "2") (pinfunction "2_2") (pintype "input"))
      (node (ref "C6") (pin "2") (pinfunction "2_2") (pintype "input"))
      (node (ref "C7") (pin "2") (pinfunction "2_2") (pintype "input"))
      (node (ref "C9") (pin "2") (pinfunction "2_2") (pintype "input"))
      (node (ref "DCOUT1") (pin "2") (pinfunction "2_2") (pintype "input"))
      (node (ref "FB1") (pin "1") (pinfunction "1_1") (pintype "input"))
      (node (ref "LED5V") (pin "C") (pinfunction "C_C") (pintype "input"))
      (node (ref "LEDSTEER") (pin "C") (pinfunction "C_C") (pintype "input"))
      (node (ref "R2") (pin "1") (pinfunction "1_1") (pintype "input"))
      (node (ref "R4") (pin "2") (pinfunction "2_2") (pintype "input"))
      (node (ref "R8") (pin "2") (pinfunction "2_2") (pintype "input"))
      (node (ref "STEER1") (pin "3") (pinfunction "3_3") (pintype "input"))
      (node (ref "U1") (pin "2") (pinfunction "GND_2") (pintype "input"))
      (node (ref "U2") (pin "0") (pinfunction "EP/GND_0") (pintype "input"))
      (node (ref "U2") (pin "7") (pinfunction "GND_7") (pintype "input"))
      (node (ref "U3") (pin "2") (pinfunction "GND_2") (pintype "input"))
      (node (ref "电机信号1") (pin "3") (pinfunction "3_3") (pintype "input"))
      (node (ref "电机信号1") (pin "4") (pinfunction "4_4") (pintype "input"))
    )
    (net (code "59") (name "GNDCAM") (class "Default")
      (node (ref "C19") (pin "2") (pinfunction "2_2") (pintype "input"))
      (node (ref "C20") (pin "2") (pinfunction "2_2") (pintype "input"))
      (node (ref "FB2") (pin "2") (pinfunction "2_2") (pintype "input"))
      (node (ref "LEDCAM") (pin "C") (pinfunction "C_C") (pintype "input"))
      (node (ref "摄像头接口") (pin "14") (pinfunction "14_14") (pintype "input"))
      (node (ref "摄像头接口") (pin "4") (pinfunction "4_4") (pintype "input"))
    )
    (net (code "60") (name "GNDOP") (class "Default")
      (node (ref "C23") (pin "2") (pinfunction "2_2") (pintype "input"))
      (node (ref "C24") (pin "2") (pinfunction "2_2") (pintype "input"))
      (node (ref "FB3") (pin "2") (pinfunction "2_2") (pintype "input"))
      (node (ref "LEDOP") (pin "C") (pinfunction "C_C") (pintype "input"))
      (node (ref "电磁接口2") (pin "2") (pinfunction "2_2") (pintype "input"))
      (node (ref "电磁接口2") (pin "5") (pinfunction "5_5") (pintype "input"))
      (node (ref "电磁运放模块1") (pin "2") (pinfunction "GND_2") (pintype "input"))
      (node (ref "电磁运放模块1") (pin "5") (pinfunction "GND_5") (pintype "input"))
      (node (ref "电磁运放模块1") (pin "9") (pinfunction "GND_9") (pintype "input"))
    )
    (net (code "61") (name "Net-(B1-+)") (class "Default")
      (node (ref "B1") (pin "1") (pinfunction "+_1") (pintype "input"))
      (node (ref "R22") (pin "2") (pinfunction "2_2") (pintype "input"))
    )
    (net (code "62") (name "Net-(B1--)") (class "Default")
      (node (ref "B1") (pin "2") (pinfunction "-_2") (pintype "input"))
      (node (ref "Q2") (pin "3") (pinfunction "C_3") (pintype "input"))
    )
    (net (code "63") (name "Net-(C7-Pad1)") (class "Default")
      (node (ref "C7") (pin "1") (pinfunction "1_1") (pintype "input"))
      (node (ref "R5") (pin "2") (pinfunction "2_2") (pintype "input"))
    )
    (net (code "64") (name "Net-(D1-PadA)") (class "Default")
      (node (ref "D1") (pin "A") (pinfunction "A_A") (pintype "input"))
      (node (ref "ON/OFF") (pin "3") (pintype "input"))
      (node (ref "R2") (pin "2") (pinfunction "2_2") (pintype "input"))
    )
    (net (code "65") (name "Net-(D1-PadK)") (class "Default")
      (node (ref "D1") (pin "K") (pinfunction "K_K") (pintype "input"))
      (node (ref "ON/OFF") (pin "1") (pintype "input"))
      (node (ref "R1") (pin "2") (pinfunction "2_2") (pintype "input"))
    )
    (net (code "66") (name "Net-(LED3V3-PadA)") (class "Default")
      (node (ref "LED3V3") (pin "A") (pinfunction "A_A") (pintype "input"))
      (node (ref "R12") (pin "2") (pinfunction "2_2") (pintype "input"))
    )
    (net (code "67") (name "Net-(LED5V-PadA)") (class "Default")
      (node (ref "LED5V") (pin "A") (pinfunction "A_A") (pintype "input"))
      (node (ref "R11") (pin "2") (pinfunction "2_2") (pintype "input"))
    )
    (net (code "68") (name "Net-(LEDCAM-PadA)") (class "Default")
      (node (ref "LEDCAM") (pin "A") (pinfunction "A_A") (pintype "input"))
      (node (ref "R13") (pin "2") (pinfunction "2_2") (pintype "input"))
    )
    (net (code "69") (name "Net-(LEDOP-PadA)") (class "Default")
      (node (ref "LEDOP") (pin "A") (pinfunction "A_A") (pintype "input"))
      (node (ref "R33") (pin "2") (pinfunction "2_2") (pintype "input"))
    )
    (net (code "70") (name "Net-(LEDSTEER-PadA)") (class "Default")
      (node (ref "LEDSTEER") (pin "A") (pinfunction "A_A") (pintype "input"))
      (node (ref "R9") (pin "1") (pinfunction "1_1") (pintype "input"))
    )
    (net (code "71") (name "Net-(Q1-G)") (class "Default")
      (node (ref "ON/OFF") (pin "2") (pintype "input"))
      (node (ref "Q1") (pin "2") (pinfunction "G_2") (pintype "input"))
    )
    (net (code "72") (name "Net-(Q1-S)") (class "Default")
      (node (ref "Q1") (pin "3") (pinfunction "S_3") (pintype "input"))
      (node (ref "R1") (pin "1") (pinfunction "1_1") (pintype "input"))
      (node (ref "U1") (pin "1") (pinfunction "VCC_1") (pintype "input"))
    )
    (net (code "73") (name "Net-(Q2-B)") (class "Default")
      (node (ref "Q2") (pin "1") (pinfunction "B_1") (pintype "input"))
      (node (ref "R23") (pin "2") (pinfunction "2_2") (pintype "input"))
    )
    (net (code "74") (name "Net-(R7-BOT)") (class "Default")
      (node (ref "R7") (pin "2") (pinfunction "BOT_2") (pintype "input"))
      (node (ref "R8") (pin "1") (pinfunction "1_1") (pintype "input"))
      (node (ref "U2") (pin "5") (pinfunction "FB_5") (pintype "input"))
    )
    (net (code "75") (name "Net-(R7-TOP)") (class "Default")
      (node (ref "R6") (pin "2") (pinfunction "2_2") (pintype "input"))
      (node (ref "R7") (pin "1") (pinfunction "TOP_1") (pintype "input"))
      (node (ref "R7") (pin "ADJ") (pinfunction "ADJ_ADJ") (pintype "input"))
    )
    (net (code "76") (name "Net-(R10-Pad1)") (class "Default")
      (node (ref "R10") (pin "1") (pinfunction "1_1") (pintype "input"))
      (node (ref "STEER1") (pin "1") (pinfunction "1_1") (pintype "input"))
    )
    (net (code "77") (name "Net-(R14-Pad2)") (class "Default")
      (node (ref "R14") (pin "2") (pinfunction "2_2") (pintype "input"))
      (node (ref "R35") (pin "1") (pinfunction "1_1") (pintype "input"))
      (node (ref "S1") (pin "2") (pinfunction "2_2") (pintype "input"))
    )
    (net (code "78") (name "Net-(R15-Pad2)") (class "Default")
      (node (ref "R15") (pin "2") (pinfunction "2_2") (pintype "input"))
      (node (ref "R36") (pin "1") (pinfunction "1_1") (pintype "input"))
      (node (ref "S2") (pin "2") (pinfunction "2_2") (pintype "input"))
    )
    (net (code "79") (name "Net-(R16-Pad2)") (class "Default")
      (node (ref "R16") (pin "2") (pinfunction "2_2") (pintype "input"))
      (node (ref "R37") (pin "1") (pinfunction "1_1") (pintype "input"))
      (node (ref "S3") (pin "2") (pinfunction "2_2") (pintype "input"))
    )
    (net (code "80") (name "Net-(R17-Pad2)") (class "Default")
      (node (ref "R17") (pin "2") (pinfunction "2_2") (pintype "input"))
      (node (ref "R38") (pin "1") (pinfunction "1_1") (pintype "input"))
      (node (ref "S4") (pin "2") (pinfunction "2_2") (pintype "input"))
    )
    (net (code "81") (name "Net-(R25-Pad1)") (class "Default")
      (node (ref "R25") (pin "1") (pinfunction "1_1") (pintype "input"))
      (node (ref "电机信号1") (pin "5") (pinfunction "5_5") (pintype "input"))
    )
    (net (code "82") (name "Net-(R26-Pad1)") (class "Default")
      (node (ref "R26") (pin "1") (pinfunction "1_1") (pintype "input"))
      (node (ref "电机信号1") (pin "1") (pinfunction "1_1") (pintype "input"))
    )
    (net (code "83") (name "Net-(R27-Pad1)") (class "Default")
      (node (ref "R27") (pin "1") (pinfunction "1_1") (pintype "input"))
      (node (ref "电机信号1") (pin "6") (pinfunction "6_6") (pintype "input"))
    )
    (net (code "84") (name "Net-(R28-Pad1)") (class "Default")
      (node (ref "R28") (pin "1") (pinfunction "1_1") (pintype "input"))
      (node (ref "电机信号1") (pin "2") (pinfunction "2_2") (pintype "input"))
    )
    (net (code "85") (name "Net-(U2-BOOT)") (class "Default")
      (node (ref "C4") (pin "1") (pinfunction "1_1") (pintype "input"))
      (node (ref "U2") (pin "1") (pinfunction "BOOT_1") (pintype "input"))
    )
    (net (code "86") (name "Net-(U2-COMP)") (class "Default")
      (node (ref "R5") (pin "1") (pinfunction "1_1") (pintype "input"))
      (node (ref "U2") (pin "6") (pinfunction "COMP_6") (pintype "input"))
    )
    (net (code "87") (name "Net-(U2-RT{slash}CLK)") (class "Default")
      (node (ref "R4") (pin "1") (pinfunction "1_1") (pintype "input"))
      (node (ref "U2") (pin "4") (pinfunction "RT/CLK_4") (pintype "input"))
    )
    (net (code "88") (name "Net-(U2-SW)") (class "Default")
      (node (ref "C4") (pin "2") (pinfunction "2_2") (pintype "input"))
      (node (ref "L1") (pin "1") (pinfunction "1_1") (pintype "input"))
      (node (ref "U2") (pin "8") (pinfunction "SW_8") (pintype "input"))
    )
    (net (code "89") (name "Net-(U3-VIN)") (class "Default")
      (node (ref "C10") (pin "1") (pinfunction "1_1") (pintype "input"))
      (node (ref "C9") (pin "1") (pinfunction "1_1") (pintype "input"))
      (node (ref "D2") (pin "K") (pinfunction "K_K") (pintype "input"))
      (node (ref "U3") (pin "1") (pinfunction "VIN_1") (pintype "input"))
    )
    (net (code "90") (name "Net-(电磁运放模块1-IN1)") (class "Default")
      (node (ref "电磁接口2") (pin "1") (pinfunction "1_1") (pintype "input"))
      (node (ref "电磁运放模块1") (pin "6") (pinfunction "IN1_6") (pintype "input"))
    )
    (net (code "91") (name "Net-(电磁运放模块1-IN2)") (class "Default")
      (node (ref "电磁接口2") (pin "3") (pinfunction "3_3") (pintype "input"))
      (node (ref "电磁运放模块1") (pin "4") (pinfunction "IN2_4") (pintype "input"))
    )
    (net (code "92") (name "Net-(电磁运放模块1-IN3)") (class "Default")
      (node (ref "电磁接口2") (pin "4") (pinfunction "4_4") (pintype "input"))
      (node (ref "电磁运放模块1") (pin "3") (pinfunction "IN3_3") (pintype "input"))
    )
    (net (code "93") (name "Net-(电磁运放模块1-IN4)") (class "Default")
      (node (ref "电磁接口2") (pin "6") (pinfunction "6_6") (pintype "input"))
      (node (ref "电磁运放模块1") (pin "1") (pinfunction "IN4_1") (pintype "input"))
    )
    (net (code "94") (name "VCC3V3") (class "Default")
      (node (ref "C15") (pin "1") (pinfunction "1_1") (pintype "input"))
      (node (ref "C16") (pin "1") (pinfunction "1_1") (pintype "input"))
      (node (ref "R12") (pin "1") (pinfunction "1_1") (pintype "input"))
      (node (ref "R14") (pin "1") (pinfunction "1_1") (pintype "input"))
      (node (ref "R15") (pin "1") (pinfunction "1_1") (pintype "input"))
      (node (ref "R16") (pin "1") (pinfunction "1_1") (pintype "input"))
      (node (ref "R17") (pin "1") (pinfunction "1_1") (pintype "input"))
      (node (ref "R22") (pin "1") (pinfunction "1_1") (pintype "input"))
      (node (ref "U4") (pin "5") (pinfunction "OUT_5") (pintype "input"))
      (node (ref "停车检测") (pin "2") (pinfunction "2_2") (pintype "input"))
      (node (ref "姿态传感器") (pin "1") (pinfunction "1_1") (pintype "input"))
      (node (ref "屏幕接口") (pin "4") (pinfunction "4_4") (pintype "input"))
      (node (ref "编码器1") (pin "2") (pinfunction "2_2") (pintype "input"))
      (node (ref "编码器2") (pin "2") (pinfunction "2_2") (pintype "input"))
    )
    (net (code "95") (name "VCC5V") (class "Default")
      (node (ref "C11") (pin "1") (pinfunction "1_1") (pintype "input"))
      (node (ref "C12") (pin "1") (pinfunction "1_1") (pintype "input"))
      (node (ref "C13") (pin "1") (pinfunction "1_1") (pintype "input"))
      (node (ref "C14") (pin "1") (pinfunction "1_1") (pintype "input"))
      (node (ref "C17") (pin "1") (pinfunction "1_1") (pintype "input"))
      (node (ref "C18") (pin "1") (pinfunction "1_1") (pintype "input"))
      (node (ref "C21") (pin "1") (pinfunction "1_1") (pintype "input"))
      (node (ref "C22") (pin "1") (pinfunction "1_1") (pintype "input"))
      (node (ref "R11") (pin "1") (pinfunction "1_1") (pintype "input"))
      (node (ref "U3") (pin "3") (pinfunction "VOUT_3") (pintype "input"))
      (node (ref "U4") (pin "1") (pinfunction "IN_1") (pintype "input"))
      (node (ref "U4") (pin "3") (pinfunction "EN_3") (pintype "input"))
      (node (ref "U5") (pin "1") (pinfunction "IN_1") (pintype "input"))
      (node (ref "U5") (pin "3") (pinfunction "EN_3") (pintype "input"))
      (node (ref "U6") (pin "1") (pinfunction "IN_1") (pintype "input"))
      (node (ref "U6") (pin "3") (pinfunction "EN_3") (pintype "input"))
      (node (ref "U7") (pin "5") (pinfunction "5V_5") (pintype "input"))
      (node (ref "U7") (pin "6") (pinfunction "5V_6") (pintype "input"))
      (node (ref "有去") (pin "1") (pinfunction "1_1") (pintype "input"))
      (node (ref "有来") (pin "1") (pinfunction "1_1") (pintype "input"))
      (node (ref "蓝牙串口模块1") (pin "7") (pinfunction "7_7") (pintype "input"))
    )
    (net (code "96") (name "VCCBAT") (class "Default")
      (node (ref "C1") (pin "1") (pinfunction "1_1") (pintype "input"))
      (node (ref "C2") (pin "1") (pinfunction "1_1") (pintype "input"))
      (node (ref "C3") (pin "1") (pinfunction "1_1") (pintype "input"))
      (node (ref "D2") (pin "A") (pinfunction "A_A") (pintype "input"))
      (node (ref "DCOUT1") (pin "1") (pinfunction "1_1") (pintype "input"))
      (node (ref "Q1") (pin "1") (pinfunction "D_1") (pintype "input"))
      (node (ref "U2") (pin "2") (pinfunction "VIN_2") (pintype "input"))
      (node (ref "U2") (pin "3") (pinfunction "EN_3") (pintype "input"))
    )
    (net (code "97") (name "VCCCAM") (class "Default")
      (node (ref "C19") (pin "1") (pinfunction "1_1") (pintype "input"))
      (node (ref "C20") (pin "1") (pinfunction "1_1") (pintype "input"))
      (node (ref "R13") (pin "1") (pinfunction "1_1") (pintype "input"))
      (node (ref "U5") (pin "5") (pinfunction "OUT_5") (pintype "input"))
      (node (ref "摄像头接口") (pin "16") (pinfunction "16_16") (pintype "input"))
    )
    (net (code "98") (name "VCCOP") (class "Default")
      (node (ref "C23") (pin "1") (pinfunction "1_1") (pintype "input"))
      (node (ref "C24") (pin "1") (pinfunction "1_1") (pintype "input"))
      (node (ref "R33") (pin "1") (pinfunction "1_1") (pintype "input"))
      (node (ref "U6") (pin "5") (pinfunction "OUT_5") (pintype "input"))
      (node (ref "电磁运放模块1") (pin "8") (pinfunction "VCC_8") (pintype "input"))
    )
    (net (code "99") (name "VCCSTEER") (class "Default")
      (node (ref "C5") (pin "1") (pinfunction "1_1") (pintype "input"))
      (node (ref "C6") (pin "1") (pinfunction "1_1") (pintype "input"))
      (node (ref "L1") (pin "2") (pinfunction "2_2") (pintype "input"))
      (node (ref "R6") (pin "1") (pinfunction "1_1") (pintype "input"))
      (node (ref "R9") (pin "2") (pinfunction "2_2") (pintype "input"))
      (node (ref "STEER1") (pin "2") (pinfunction "2_2") (pintype "input"))
    )
    (net (code "100") (name "unconnected-(M1-Pad1)") (class "Default")
      (node (ref "M1") (pin "1") (pinfunction "1_1") (pintype "input+no_connect"))
    )
    (net (code "101") (name "unconnected-(M2-Pad1)") (class "Default")
      (node (ref "M2") (pin "1") (pinfunction "1_1") (pintype "input+no_connect"))
    )
    (net (code "102") (name "unconnected-(M3-Pad1)") (class "Default")
      (node (ref "M3") (pin "1") (pinfunction "1_1") (pintype "input+no_connect"))
    )
    (net (code "103") (name "unconnected-(M4-Pad1)") (class "Default")
      (node (ref "M4") (pin "1") (pinfunction "1_1") (pintype "input+no_connect"))
    )
    (net (code "104") (name "unconnected-(U4-NC-Pad4)") (class "Default")
      (node (ref "U4") (pin "4") (pinfunction "NC_4") (pintype "input+no_connect"))
    )
    (net (code "105") (name "unconnected-(U5-NC-Pad4)") (class "Default")
      (node (ref "U5") (pin "4") (pinfunction "NC_4") (pintype "input+no_connect"))
    )
    (net (code "106") (name "unconnected-(U6-NC-Pad4)") (class "Default")
      (node (ref "U6") (pin "4") (pinfunction "NC_4") (pintype "input+no_connect"))
    )
    (net (code "107") (name "unconnected-(U7-3V3-Pad3)") (class "Default")
      (node (ref "U7") (pin "3") (pinfunction "3V3_3") (pintype "input+no_connect"))
    )
    (net (code "108") (name "unconnected-(U7-3V3-Pad4)") (class "Default")
      (node (ref "U7") (pin "4") (pinfunction "3V3_4") (pintype "input+no_connect"))
    )
    (net (code "109") (name "unconnected-(U7-B10-Pad59)") (class "Default")
      (node (ref "U7") (pin "59") (pinfunction "B10_59") (pintype "input+no_connect"))
    )
    (net (code "110") (name "unconnected-(U7-B11-Pad62)") (class "Default")
      (node (ref "U7") (pin "62") (pinfunction "B11_62") (pintype "input+no_connect"))
    )
    (net (code "111") (name "unconnected-(U7-B14-Pad63)") (class "Default")
      (node (ref "U7") (pin "63") (pinfunction "B14_63") (pintype "input+no_connect"))
    )
    (net (code "112") (name "unconnected-(U7-C2-Pad36)") (class "Default")
      (node (ref "U7") (pin "36") (pinfunction "C2_36") (pintype "input+no_connect"))
    )
    (net (code "113") (name "unconnected-(U7-C3-Pad37)") (class "Default")
      (node (ref "U7") (pin "37") (pinfunction "C3_37") (pintype "input+no_connect"))
    )
    (net (code "114") (name "unconnected-(U7-C4-Pad46)") (class "Default")
      (node (ref "U7") (pin "46") (pinfunction "C4_46") (pintype "input+no_connect"))
    )
    (net (code "115") (name "unconnected-(U7-C5-Pad47)") (class "Default")
      (node (ref "U7") (pin "47") (pinfunction "C5_47") (pintype "input+no_connect"))
    )
    (net (code "116") (name "unconnected-(U7-C6-Pad73)") (class "Default")
      (node (ref "U7") (pin "73") (pinfunction "C6_73") (pintype "input+no_connect"))
    )
    (net (code "117") (name "unconnected-(U7-C7-Pad76)") (class "Default")
      (node (ref "U7") (pin "76") (pinfunction "C7_76") (pintype "input+no_connect"))
    )
    (net (code "118") (name "unconnected-(U7-D1-Pad12)") (class "Default")
      (node (ref "U7") (pin "12") (pinfunction "D1_12") (pintype "input+no_connect"))
    )
    (net (code "119") (name "unconnected-(U7-D3-Pad14)") (class "Default")
      (node (ref "U7") (pin "14") (pinfunction "D3_14") (pintype "input+no_connect"))
    )
    (net (code "120") (name "unconnected-(U7-D5-Pad16)") (class "Default")
      (node (ref "U7") (pin "16") (pinfunction "D5_16") (pintype "input+no_connect"))
    )
    (net (code "121") (name "unconnected-(U7-D6-Pad17)") (class "Default")
      (node (ref "U7") (pin "17") (pinfunction "D6_17") (pintype "input+no_connect"))
    )
    (net (code "122") (name "unconnected-(U7-D12-Pad69)") (class "Default")
      (node (ref "U7") (pin "69") (pinfunction "D12_69") (pintype "input+no_connect"))
    )
    (net (code "123") (name "unconnected-(U7-D13-Pad72)") (class "Default")
      (node (ref "U7") (pin "72") (pinfunction "D13_72") (pintype "input+no_connect"))
    )
    (net (code "124") (name "unconnected-(U7-D14-Pad71)") (class "Default")
      (node (ref "U7") (pin "71") (pinfunction "D14_71") (pintype "input+no_connect"))
    )
    (net (code "125") (name "unconnected-(U7-D15-Pad74)") (class "Default")
      (node (ref "U7") (pin "74") (pinfunction "D15_74") (pintype "input+no_connect"))
    )
    (net (code "126") (name "unconnected-(U7-E10-Pad53)") (class "Default")
      (node (ref "U7") (pin "53") (pinfunction "E10_53") (pintype "input+no_connect"))
    )
    (net (code "127") (name "unconnected-(姿态传感器-Pad7)") (class "Default")
      (node (ref "姿态传感器") (pin "7") (pinfunction "7_7") (pintype "input+no_connect"))
    )
    (net (code "128") (name "unconnected-(姿态传感器-Pad8)") (class "Default")
      (node (ref "姿态传感器") (pin "8") (pinfunction "8_8") (pintype "input+no_connect"))
    )
    (net (code "129") (name "unconnected-(有去-Pad4)") (class "Default")
      (node (ref "有去") (pin "4") (pinfunction "4_4") (pintype "input+no_connect"))
    )
    (net (code "130") (name "unconnected-(编码器1-Pad5)") (class "Default")
      (node (ref "编码器1") (pin "5") (pinfunction "5_5") (pintype "input+no_connect"))
    )
    (net (code "131") (name "unconnected-(编码器1-Pad6)") (class "Default")
      (node (ref "编码器1") (pin "6") (pinfunction "6_6") (pintype "input+no_connect"))
    )
    (net (code "132") (name "unconnected-(编码器2-Pad5)") (class "Default")
      (node (ref "编码器2") (pin "5") (pinfunction "5_5") (pintype "input+no_connect"))
    )
    (net (code "133") (name "unconnected-(编码器2-Pad6)") (class "Default")
      (node (ref "编码器2") (pin "6") (pinfunction "6_6") (pintype "input+no_connect"))
    )
    (net (code "134") (name "unconnected-(蓝牙串口模块1-Pad2)") (class "Default")
      (node (ref "蓝牙串口模块1") (pin "2") (pinfunction "2_2") (pintype "input+no_connect"))
    )
    (net (code "135") (name "unconnected-(蓝牙串口模块1-Pad8)") (class "Default")
      (node (ref "蓝牙串口模块1") (pin "8") (pinfunction "8_8") (pintype "input+no_connect"))
    )
  )
)
